# ethernet_hdmi.net
KiCad netlist of a schematic drawn in Altium Designer
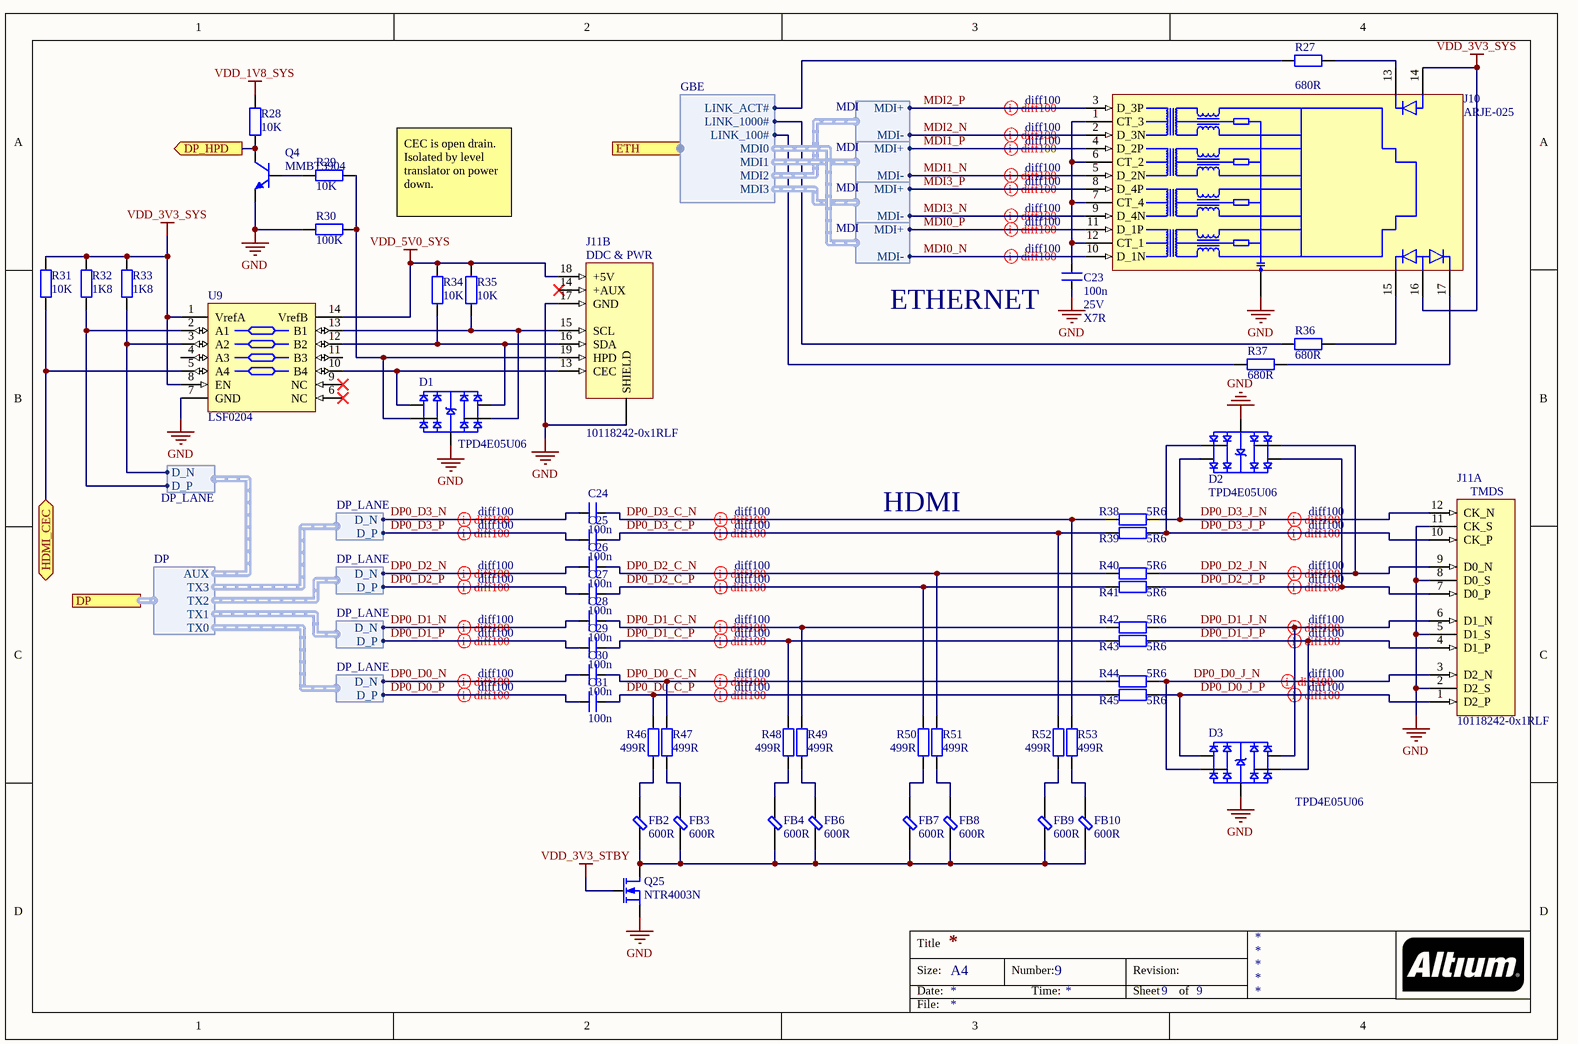
[diagram p0: ethernet_hdmi.SchDoc]

(export (version "E")
  (design (tool "Eeschema 10.0.6"))
  (components
    (comp (ref "C23")
      (value "100n")
      (footprint "C1005[0402]")
      (description "Capacitor")
      (fields (field (name "VOLTAGE") "25V") (field (name "TYPE") "X7R") (field (name "Comment") "cap"))
      (libsource (lib "gpa_passives") (part "cap"))
    )
    (comp (ref "C24")
      (value "100n")
      (footprint "C1005[0402]")
      (description "Capacitor")
      (fields (field (name "VOLTAGE") "25V") (field (name "Comment") "cap"))
      (libsource (lib "gpa_passives") (part "cap"))
    )
    (comp (ref "C25")
      (value "100n")
      (footprint "C1005[0402]")
      (description "Capacitor")
      (fields (field (name "VOLTAGE") "25V") (field (name "Comment") "cap"))
      (libsource (lib "gpa_passives") (part "cap"))
    )
    (comp (ref "C26")
      (value "100n")
      (footprint "C1005[0402]")
      (description "Capacitor")
      (fields (field (name "VOLTAGE") "25V") (field (name "Comment") "cap"))
      (libsource (lib "gpa_passives") (part "cap"))
    )
    (comp (ref "C27")
      (value "100n")
      (footprint "C1005[0402]")
      (description "Capacitor")
      (fields (field (name "VOLTAGE") "25V") (field (name "Comment") "cap"))
      (libsource (lib "gpa_passives") (part "cap"))
    )
    (comp (ref "C28")
      (value "100n")
      (footprint "C1005[0402]")
      (description "Capacitor")
      (fields (field (name "VOLTAGE") "25V") (field (name "Comment") "cap"))
      (libsource (lib "gpa_passives") (part "cap"))
    )
    (comp (ref "C29")
      (value "100n")
      (footprint "C1005[0402]")
      (description "Capacitor")
      (fields (field (name "VOLTAGE") "25V") (field (name "Comment") "cap"))
      (libsource (lib "gpa_passives") (part "cap"))
    )
    (comp (ref "C30")
      (value "100n")
      (footprint "C1005[0402]")
      (description "Capacitor")
      (fields (field (name "VOLTAGE") "25V") (field (name "Comment") "cap"))
      (libsource (lib "gpa_passives") (part "cap"))
    )
    (comp (ref "C31")
      (value "100n")
      (footprint "C1005[0402]")
      (description "Capacitor")
      (fields (field (name "VOLTAGE") "25V") (field (name "Comment") "cap"))
      (libsource (lib "gpa_passives") (part "cap"))
    )
    (comp (ref "D1")
      (value "TPD4E05U06")
      (footprint "TI_PSON50P100X55-10N")
      (libsource (lib "gpa_ti") (part "tpd4e05u06"))
    )
    (comp (ref "D2")
      (value "TPD4E05U06")
      (footprint "TI_PSON50P100X55-10N")
      (libsource (lib "gpa_ti") (part "tpd4e05u06"))
    )
    (comp (ref "D3")
      (value "TPD4E05U06")
      (footprint "TI_PSON50P100X55-10N")
      (libsource (lib "gpa_ti") (part "tpd4e05u06"))
    )
    (comp (ref "FB2")
      (value "600R")
      (footprint "FBC1608X07N")
      (description "Ferrite bead")
      (libsource (lib "gpa_passives") (part "ferrite_bead"))
    )
    (comp (ref "FB3")
      (value "600R")
      (footprint "FBC1608X07N")
      (description "Ferrite bead")
      (libsource (lib "gpa_passives") (part "ferrite_bead"))
    )
    (comp (ref "FB4")
      (value "600R")
      (footprint "FBC1608X07N")
      (description "Ferrite bead")
      (libsource (lib "gpa_passives") (part "ferrite_bead"))
    )
    (comp (ref "FB6")
      (value "600R")
      (footprint "FBC1608X07N")
      (description "Ferrite bead")
      (libsource (lib "gpa_passives") (part "ferrite_bead"))
    )
    (comp (ref "FB7")
      (value "600R")
      (footprint "FBC1608X07N")
      (description "Ferrite bead")
      (libsource (lib "gpa_passives") (part "ferrite_bead"))
    )
    (comp (ref "FB8")
      (value "600R")
      (footprint "FBC1608X07N")
      (description "Ferrite bead")
      (libsource (lib "gpa_passives") (part "ferrite_bead"))
    )
    (comp (ref "FB9")
      (value "600R")
      (footprint "FBC1608X07N")
      (description "Ferrite bead")
      (libsource (lib "gpa_passives") (part "ferrite_bead"))
    )
    (comp (ref "FB10")
      (value "600R")
      (footprint "FBC1608X07N")
      (description "Ferrite bead")
      (libsource (lib "gpa_passives") (part "ferrite_bead"))
    )
    (comp (ref "J10")
      (value "ARJE-025")
      (footprint "abraconn_rj45_arje0025")
      (description "RJ45 with integrated magnetics")
      (libsource (lib "gpa_connectors") (part "geth_wmagnetics"))
    )
    (comp (ref "J11")
      (value "10118242-0x1RLF")
      (footprint "molex_hdmi")
      (libsource (lib "gpa_connectors") (part "hdmi"))
    )
    (comp (ref "Q4")
      (value "MMBT3904")
      (footprint "NPN_SOT95P230X110-3N")
      (description "NPN Bipolar Transistor")
      (fields (field (name "PUBLISHER") "Altium Limited"))
      (libsource (lib "gpa_actives") (part "npn_bipolar"))
    )
    (comp (ref "Q25")
      (value "NTR4003N")
      (footprint "NCH_SOT95P237X110-3N")
      (libsource (lib "gpa_actives") (part "nch_mosfet"))
    )
    (comp (ref "R27")
      (value "680R")
      (footprint "R1005[0402]")
      (description "Resistor")
      (fields (field (name "Comment") "res"))
      (libsource (lib "") (part "res_1"))
    )
    (comp (ref "R28")
      (value "10K")
      (footprint "R1005[0402]")
      (description "Resistor")
      (fields (field (name "Comment") "res"))
      (libsource (lib "gpa_passives") (part "res"))
    )
    (comp (ref "R29")
      (value "10K")
      (footprint "R1005[0402]")
      (description "Resistor")
      (fields (field (name "Comment") "res"))
      (libsource (lib "") (part "res_1"))
    )
    (comp (ref "R30")
      (value "100K")
      (footprint "R1005[0402]")
      (description "Resistor")
      (fields (field (name "Comment") "res"))
      (libsource (lib "") (part "res_1"))
    )
    (comp (ref "R31")
      (value "10K")
      (footprint "R1005[0402]")
      (description "Resistor")
      (fields (field (name "Comment") "res"))
      (libsource (lib "gpa_passives") (part "res"))
    )
    (comp (ref "R32")
      (value "1K8")
      (footprint "R1005[0402]")
      (description "Resistor")
      (fields (field (name "Comment") "res"))
      (libsource (lib "gpa_passives") (part "res"))
    )
    (comp (ref "R33")
      (value "1K8")
      (footprint "R1005[0402]")
      (description "Resistor")
      (fields (field (name "Comment") "res"))
      (libsource (lib "gpa_passives") (part "res"))
    )
    (comp (ref "R34")
      (value "10K")
      (footprint "R1005[0402]")
      (description "Resistor")
      (fields (field (name "Comment") "res"))
      (libsource (lib "gpa_passives") (part "res"))
    )
    (comp (ref "R35")
      (value "10K")
      (footprint "R1005[0402]")
      (description "Resistor")
      (fields (field (name "Comment") "res"))
      (libsource (lib "gpa_passives") (part "res"))
    )
    (comp (ref "R36")
      (value "680R")
      (footprint "R1005[0402]")
      (description "Resistor")
      (fields (field (name "Comment") "res"))
      (libsource (lib "") (part "res_2"))
    )
    (comp (ref "R37")
      (value "680R")
      (footprint "R1005[0402]")
      (description "Resistor")
      (fields (field (name "Comment") "res"))
      (libsource (lib "") (part "res_1"))
    )
    (comp (ref "R38")
      (value "5R6")
      (footprint "R1005[0402]")
      (description "Resistor")
      (fields (field (name "Comment") "res"))
      (libsource (lib "") (part "res_2"))
    )
    (comp (ref "R39")
      (value "5R6")
      (footprint "R1005[0402]")
      (description "Resistor")
      (fields (field (name "Comment") "res"))
      (libsource (lib "") (part "res_2"))
    )
    (comp (ref "R40")
      (value "5R6")
      (footprint "R1005[0402]")
      (description "Resistor")
      (fields (field (name "Comment") "res"))
      (libsource (lib "") (part "res_2"))
    )
    (comp (ref "R41")
      (value "5R6")
      (footprint "R1005[0402]")
      (description "Resistor")
      (fields (field (name "Comment") "res"))
      (libsource (lib "") (part "res_2"))
    )
    (comp (ref "R42")
      (value "5R6")
      (footprint "R1005[0402]")
      (description "Resistor")
      (fields (field (name "Comment") "res"))
      (libsource (lib "") (part "res_2"))
    )
    (comp (ref "R43")
      (value "5R6")
      (footprint "R1005[0402]")
      (description "Resistor")
      (fields (field (name "Comment") "res"))
      (libsource (lib "") (part "res_2"))
    )
    (comp (ref "R44")
      (value "5R6")
      (footprint "R1005[0402]")
      (description "Resistor")
      (fields (field (name "Comment") "res"))
      (libsource (lib "") (part "res_2"))
    )
    (comp (ref "R45")
      (value "5R6")
      (footprint "R1005[0402]")
      (description "Resistor")
      (fields (field (name "Comment") "res"))
      (libsource (lib "") (part "res_2"))
    )
    (comp (ref "R46")
      (value "499R")
      (footprint "R1005[0402]")
      (description "Resistor")
      (fields (field (name "Comment") "res"))
      (libsource (lib "gpa_passives") (part "res"))
    )
    (comp (ref "R47")
      (value "499R")
      (footprint "R1005[0402]")
      (description "Resistor")
      (fields (field (name "Comment") "res"))
      (libsource (lib "gpa_passives") (part "res"))
    )
    (comp (ref "R48")
      (value "499R")
      (footprint "R1005[0402]")
      (description "Resistor")
      (fields (field (name "Comment") "res"))
      (libsource (lib "gpa_passives") (part "res"))
    )
    (comp (ref "R49")
      (value "499R")
      (footprint "R1005[0402]")
      (description "Resistor")
      (fields (field (name "Comment") "res"))
      (libsource (lib "gpa_passives") (part "res"))
    )
    (comp (ref "R50")
      (value "499R")
      (footprint "R1005[0402]")
      (description "Resistor")
      (fields (field (name "Comment") "res"))
      (libsource (lib "gpa_passives") (part "res"))
    )
    (comp (ref "R51")
      (value "499R")
      (footprint "R1005[0402]")
      (description "Resistor")
      (fields (field (name "Comment") "res"))
      (libsource (lib "gpa_passives") (part "res"))
    )
    (comp (ref "R52")
      (value "499R")
      (footprint "R1005[0402]")
      (description "Resistor")
      (fields (field (name "Comment") "res"))
      (libsource (lib "gpa_passives") (part "res"))
    )
    (comp (ref "R53")
      (value "499R")
      (footprint "R1005[0402]")
      (description "Resistor")
      (fields (field (name "Comment") "res"))
      (libsource (lib "gpa_passives") (part "res"))
    )
    (comp (ref "U9")
      (value "LSF0204")
      (footprint "TI_TSOP65P640X120-14N")
      (libsource (lib "gpa_ti") (part "lsf0204"))
    )
  )
  (nets
    (net (code "6") (name "/DP0_D0_C_N") (class "Default")
      (node (ref "C30") (pin "1") (pinfunction "1_1") (pintype "passive"))
      (node (ref "R44") (pin "1") (pinfunction "1_1") (pintype "passive"))
      (node (ref "R47") (pin "2") (pinfunction "2_2") (pintype "passive"))
    )
    (net (code "7") (name "/DP0_D0_C_P") (class "Default")
      (node (ref "C31") (pin "1") (pinfunction "1_1") (pintype "passive"))
      (node (ref "R45") (pin "1") (pinfunction "1_1") (pintype "passive"))
      (node (ref "R46") (pin "2") (pinfunction "2_2") (pintype "passive"))
    )
    (net (code "8") (name "/DP0_D0_J_N") (class "Default")
      (node (ref "D3") (pin "4") (pinfunction "D2-_4") (pintype "passive"))
      (node (ref "J11") (pin "3") (pinfunction "D2_N_3") (pintype "input"))
      (node (ref "R44") (pin "2") (pinfunction "2_2") (pintype "passive"))
    )
    (net (code "9") (name "/DP0_D0_J_P") (class "Default")
      (node (ref "D3") (pin "5") (pinfunction "D2+_5") (pintype "passive"))
      (node (ref "J11") (pin "1") (pinfunction "D2_P_1") (pintype "input"))
      (node (ref "R45") (pin "2") (pinfunction "2_2") (pintype "passive"))
    )
    (net (code "10") (name "/DP0_D0_N") (class "Default")
      (node (ref "C30") (pin "2") (pinfunction "2_2") (pintype "passive"))
    )
    (net (code "11") (name "/DP0_D0_P") (class "Default")
      (node (ref "C31") (pin "2") (pinfunction "2_2") (pintype "passive"))
    )
    (net (code "12") (name "/DP0_D1_C_N") (class "Default")
      (node (ref "C28") (pin "1") (pinfunction "1_1") (pintype "passive"))
      (node (ref "R42") (pin "1") (pinfunction "1_1") (pintype "passive"))
      (node (ref "R49") (pin "2") (pinfunction "2_2") (pintype "passive"))
    )
    (net (code "13") (name "/DP0_D1_C_P") (class "Default")
      (node (ref "C29") (pin "1") (pinfunction "1_1") (pintype "passive"))
      (node (ref "R43") (pin "1") (pinfunction "1_1") (pintype "passive"))
      (node (ref "R48") (pin "2") (pinfunction "2_2") (pintype "passive"))
    )
    (net (code "14") (name "/DP0_D1_J_N") (class "Default")
      (node (ref "D3") (pin "1") (pinfunction "D1+_1") (pintype "passive"))
      (node (ref "J11") (pin "6") (pinfunction "D1_N_6") (pintype "input"))
      (node (ref "R42") (pin "2") (pinfunction "2_2") (pintype "passive"))
    )
    (net (code "15") (name "/DP0_D1_J_P") (class "Default")
      (node (ref "D3") (pin "2") (pinfunction "D1-_2") (pintype "passive"))
      (node (ref "J11") (pin "4") (pinfunction "D1_P_4") (pintype "input"))
      (node (ref "R43") (pin "2") (pinfunction "2_2") (pintype "passive"))
    )
    (net (code "16") (name "/DP0_D1_N") (class "Default")
      (node (ref "C28") (pin "2") (pinfunction "2_2") (pintype "passive"))
    )
    (net (code "17") (name "/DP0_D1_P") (class "Default")
      (node (ref "C29") (pin "2") (pinfunction "2_2") (pintype "passive"))
    )
    (net (code "18") (name "/DP0_D2_C_N") (class "Default")
      (node (ref "C26") (pin "1") (pinfunction "1_1") (pintype "passive"))
      (node (ref "R40") (pin "1") (pinfunction "1_1") (pintype "passive"))
      (node (ref "R51") (pin "2") (pinfunction "2_2") (pintype "passive"))
    )
    (net (code "19") (name "/DP0_D2_C_P") (class "Default")
      (node (ref "C27") (pin "1") (pinfunction "1_1") (pintype "passive"))
      (node (ref "R41") (pin "1") (pinfunction "1_1") (pintype "passive"))
      (node (ref "R50") (pin "2") (pinfunction "2_2") (pintype "passive"))
    )
    (net (code "20") (name "/DP0_D2_J_N") (class "Default")
      (node (ref "D2") (pin "2") (pinfunction "D1-_2") (pintype "passive"))
      (node (ref "J11") (pin "9") (pinfunction "D0_N_9") (pintype "input"))
      (node (ref "R40") (pin "2") (pinfunction "2_2") (pintype "passive"))
    )
    (net (code "21") (name "/DP0_D2_J_P") (class "Default")
      (node (ref "D2") (pin "1") (pinfunction "D1+_1") (pintype "passive"))
      (node (ref "J11") (pin "7") (pinfunction "D0_P_7") (pintype "input"))
      (node (ref "R41") (pin "2") (pinfunction "2_2") (pintype "passive"))
    )
    (net (code "22") (name "/DP0_D2_N") (class "Default")
      (node (ref "C26") (pin "2") (pinfunction "2_2") (pintype "passive"))
    )
    (net (code "23") (name "/DP0_D2_P") (class "Default")
      (node (ref "C27") (pin "2") (pinfunction "2_2") (pintype "passive"))
    )
    (net (code "24") (name "/DP0_D3_C_N") (class "Default")
      (node (ref "C24") (pin "1") (pinfunction "1_1") (pintype "passive"))
      (node (ref "R38") (pin "1") (pinfunction "1_1") (pintype "passive"))
      (node (ref "R53") (pin "2") (pinfunction "2_2") (pintype "passive"))
    )
    (net (code "25") (name "/DP0_D3_C_P") (class "Default")
      (node (ref "C25") (pin "1") (pinfunction "1_1") (pintype "passive"))
      (node (ref "R39") (pin "1") (pinfunction "1_1") (pintype "passive"))
      (node (ref "R52") (pin "2") (pinfunction "2_2") (pintype "passive"))
    )
    (net (code "26") (name "/DP0_D3_J_N") (class "Default")
      (node (ref "D2") (pin "5") (pinfunction "D2+_5") (pintype "passive"))
      (node (ref "J11") (pin "12") (pinfunction "CK_N_12") (pintype "input"))
      (node (ref "R38") (pin "2") (pinfunction "2_2") (pintype "passive"))
    )
    (net (code "27") (name "/DP0_D3_J_P") (class "Default")
      (node (ref "D2") (pin "4") (pinfunction "D2-_4") (pintype "passive"))
      (node (ref "J11") (pin "10") (pinfunction "CK_P_10") (pintype "input"))
      (node (ref "R39") (pin "2") (pinfunction "2_2") (pintype "passive"))
    )
    (net (code "28") (name "/DP0_D3_N") (class "Default")
      (node (ref "C24") (pin "2") (pinfunction "2_2") (pintype "passive"))
    )
    (net (code "29") (name "/DP0_D3_P") (class "Default")
      (node (ref "C25") (pin "2") (pinfunction "2_2") (pintype "passive"))
    )
    (net (code "30") (name "/DP_HPD") (class "Default")
      (node (ref "Q4") (pin "C") (pinfunction "C_C") (pintype "passive"))
      (node (ref "R28") (pin "1") (pinfunction "1_1") (pintype "passive"))
    )
    (net (code "33") (name "/HDMI_CEC") (class "Default")
      (node (ref "R31") (pin "1") (pinfunction "1_1") (pintype "passive"))
      (node (ref "U9") (pin "5") (pinfunction "A4_5") (pintype "bidirectional"))
    )
    (net (code "34") (name "/LINK_100#") (class "Default")
      (node (ref "R37") (pin "2") (pinfunction "2_2") (pintype "passive"))
    )
    (net (code "35") (name "/LINK_1000#") (class "Default")
      (node (ref "R36") (pin "1") (pinfunction "1_1") (pintype "passive"))
    )
    (net (code "36") (name "/LINK_ACT#") (class "Default")
      (node (ref "R27") (pin "2") (pinfunction "2_2") (pintype "passive"))
    )
    (net (code "37") (name "/MDI0_N") (class "Default")
      (node (ref "J10") (pin "10") (pinfunction "D_1N_10") (pintype "input"))
    )
    (net (code "38") (name "/MDI0_P") (class "Default")
      (node (ref "J10") (pin "11") (pinfunction "D_1P_11") (pintype "input"))
    )
    (net (code "39") (name "/MDI1_N") (class "Default")
      (node (ref "J10") (pin "5") (pinfunction "D_2N_5") (pintype "input"))
    )
    (net (code "40") (name "/MDI1_P") (class "Default")
      (node (ref "J10") (pin "4") (pinfunction "D_2P_4") (pintype "input"))
    )
    (net (code "41") (name "/MDI2_N") (class "Default")
      (node (ref "J10") (pin "2") (pinfunction "D_3N_2") (pintype "input"))
    )
    (net (code "42") (name "/MDI2_P") (class "Default")
      (node (ref "J10") (pin "3") (pinfunction "D_3P_3") (pintype "input"))
    )
    (net (code "43") (name "/MDI3_N") (class "Default")
      (node (ref "J10") (pin "9") (pinfunction "D_4N_9") (pintype "input"))
    )
    (net (code "44") (name "/MDI3_P") (class "Default")
      (node (ref "J10") (pin "8") (pinfunction "D_4P_8") (pintype "input"))
    )
    (net (code "48") (name "GND") (class "Default")
      (node (ref "C23") (pin "1") (pinfunction "1_1") (pintype "passive"))
      (node (ref "D1") (pin "3") (pinfunction "GND_3") (pintype "passive"))
      (node (ref "D2") (pin "3") (pinfunction "GND_3") (pintype "passive"))
      (node (ref "D3") (pin "3") (pinfunction "GND_3") (pintype "passive"))
      (node (ref "J10") (pin "SHIELD") (pinfunction "SHIELD_SHIELD") (pintype "power_in"))
      (node (ref "J11") (pin "11") (pinfunction "CK_S_11") (pintype "power_in"))
      (node (ref "J11") (pin "17") (pinfunction "GND_17") (pintype "input"))
      (node (ref "J11") (pin "2") (pinfunction "D2_S_2") (pintype "power_in"))
      (node (ref "J11") (pin "5") (pinfunction "D1_S_5") (pintype "power_in"))
      (node (ref "J11") (pin "8") (pinfunction "D0_S_8") (pintype "power_in"))
      (node (ref "J11") (pin "SHIELD") (pinfunction "SHIELD_SHIELD") (pintype "passive"))
      (node (ref "Q25") (pin "S") (pinfunction "S_S") (pintype "passive"))
      (node (ref "Q4") (pin "E") (pinfunction "E_E") (pintype "passive"))
      (node (ref "R30") (pin "2") (pinfunction "2_2") (pintype "passive"))
      (node (ref "U9") (pin "7") (pinfunction "GND_7") (pintype "power_in"))
    )
    (net (code "49") (name "Net-(D1-D1+)") (class "Default")
      (node (ref "D1") (pin "1") (pinfunction "D1+_1") (pintype "passive"))
      (node (ref "J11") (pin "13") (pinfunction "CEC_13") (pintype "input"))
      (node (ref "U9") (pin "10") (pinfunction "B4_10") (pintype "bidirectional"))
    )
    (net (code "50") (name "Net-(D1-D1-)") (class "Default")
      (node (ref "D1") (pin "2") (pinfunction "D1-_2") (pintype "passive"))
      (node (ref "J11") (pin "19") (pinfunction "HPD_19") (pintype "input"))
      (node (ref "R29") (pin "1") (pinfunction "1_1") (pintype "passive"))
      (node (ref "R30") (pin "1") (pinfunction "1_1") (pintype "passive"))
    )
    (net (code "51") (name "Net-(D1-D2+)") (class "Default")
      (node (ref "D1") (pin "5") (pinfunction "D2+_5") (pintype "passive"))
      (node (ref "J11") (pin "16") (pinfunction "SDA_16") (pintype "input"))
      (node (ref "R34") (pin "1") (pinfunction "1_1") (pintype "passive"))
      (node (ref "U9") (pin "12") (pinfunction "B2_12") (pintype "bidirectional"))
    )
    (net (code "52") (name "Net-(D1-D2-)") (class "Default")
      (node (ref "D1") (pin "4") (pinfunction "D2-_4") (pintype "passive"))
      (node (ref "J11") (pin "15") (pinfunction "SCL_15") (pintype "input"))
      (node (ref "R35") (pin "1") (pinfunction "1_1") (pintype "passive"))
      (node (ref "U9") (pin "13") (pinfunction "B1_13") (pintype "bidirectional"))
    )
    (net (code "53") (name "Net-(FB2-Pad2)") (class "Default")
      (node (ref "FB2") (pin "2") (pinfunction "2_2") (pintype "passive"))
      (node (ref "R46") (pin "1") (pinfunction "1_1") (pintype "passive"))
    )
    (net (code "54") (name "Net-(FB3-Pad2)") (class "Default")
      (node (ref "FB3") (pin "2") (pinfunction "2_2") (pintype "passive"))
      (node (ref "R47") (pin "1") (pinfunction "1_1") (pintype "passive"))
    )
    (net (code "55") (name "Net-(FB4-Pad2)") (class "Default")
      (node (ref "FB4") (pin "2") (pinfunction "2_2") (pintype "passive"))
      (node (ref "R48") (pin "1") (pinfunction "1_1") (pintype "passive"))
    )
    (net (code "56") (name "Net-(FB6-Pad2)") (class "Default")
      (node (ref "FB6") (pin "2") (pinfunction "2_2") (pintype "passive"))
      (node (ref "R49") (pin "1") (pinfunction "1_1") (pintype "passive"))
    )
    (net (code "57") (name "Net-(FB7-Pad2)") (class "Default")
      (node (ref "FB7") (pin "2") (pinfunction "2_2") (pintype "passive"))
      (node (ref "R50") (pin "1") (pinfunction "1_1") (pintype "passive"))
    )
    (net (code "58") (name "Net-(FB8-Pad2)") (class "Default")
      (node (ref "FB8") (pin "2") (pinfunction "2_2") (pintype "passive"))
      (node (ref "R51") (pin "1") (pinfunction "1_1") (pintype "passive"))
    )
    (net (code "59") (name "Net-(FB9-Pad2)") (class "Default")
      (node (ref "FB9") (pin "2") (pinfunction "2_2") (pintype "passive"))
      (node (ref "R52") (pin "1") (pinfunction "1_1") (pintype "passive"))
    )
    (net (code "60") (name "Net-(FB10-Pad1)") (class "Default")
      (node (ref "FB10") (pin "1") (pinfunction "1_1") (pintype "passive"))
      (node (ref "FB2") (pin "1") (pinfunction "1_1") (pintype "passive"))
      (node (ref "FB3") (pin "1") (pinfunction "1_1") (pintype "passive"))
      (node (ref "FB4") (pin "1") (pinfunction "1_1") (pintype "passive"))
      (node (ref "FB6") (pin "1") (pinfunction "1_1") (pintype "passive"))
      (node (ref "FB7") (pin "1") (pinfunction "1_1") (pintype "passive"))
      (node (ref "FB8") (pin "1") (pinfunction "1_1") (pintype "passive"))
      (node (ref "FB9") (pin "1") (pinfunction "1_1") (pintype "passive"))
      (node (ref "Q25") (pin "D") (pinfunction "D_D") (pintype "passive"))
    )
    (net (code "61") (name "Net-(FB10-Pad2)") (class "Default")
      (node (ref "FB10") (pin "2") (pinfunction "2_2") (pintype "passive"))
      (node (ref "R53") (pin "1") (pinfunction "1_1") (pintype "passive"))
    )
    (net (code "62") (name "Net-(J10-CT_1)") (class "Default")
      (node (ref "C23") (pin "2") (pinfunction "2_2") (pintype "passive"))
      (node (ref "J10") (pin "1") (pinfunction "CT_3_1") (pintype "passive"))
      (node (ref "J10") (pin "12") (pinfunction "CT_1_12") (pintype "passive"))
      (node (ref "J10") (pin "6") (pinfunction "CT_2_6") (pintype "passive"))
      (node (ref "J10") (pin "7") (pinfunction "CT_4_7") (pintype "passive"))
    )
    (net (code "63") (name "Net-(J10-Pad13)") (class "Default")
      (node (ref "J10") (pin "13") (pinfunction "13_13") (pintype "passive"))
      (node (ref "R27") (pin "1") (pinfunction "1_1") (pintype "passive"))
    )
    (net (code "64") (name "Net-(J10-Pad15)") (class "Default")
      (node (ref "J10") (pin "15") (pinfunction "15_15") (pintype "passive"))
      (node (ref "R36") (pin "2") (pinfunction "2_2") (pintype "passive"))
    )
    (net (code "65") (name "Net-(J10-Pad17)") (class "Default")
      (node (ref "J10") (pin "17") (pinfunction "17_17") (pintype "passive"))
      (node (ref "R37") (pin "1") (pinfunction "1_1") (pintype "passive"))
    )
    (net (code "66") (name "Net-(Q4-PadB)") (class "Default")
      (node (ref "Q4") (pin "B") (pinfunction "B_B") (pintype "passive"))
      (node (ref "R29") (pin "2") (pinfunction "2_2") (pintype "passive"))
    )
    (net (code "67") (name "Net-(U9-A1)") (class "Default")
      (node (ref "R32") (pin "1") (pinfunction "1_1") (pintype "passive"))
      (node (ref "U9") (pin "2") (pinfunction "A1_2") (pintype "bidirectional"))
    )
    (net (code "68") (name "Net-(U9-A2)") (class "Default")
      (node (ref "R33") (pin "1") (pinfunction "1_1") (pintype "passive"))
      (node (ref "U9") (pin "3") (pinfunction "A2_3") (pintype "bidirectional"))
    )
    (net (code "69") (name "VDD_1V8_SYS") (class "Default")
      (node (ref "R28") (pin "2") (pinfunction "2_2") (pintype "passive"))
    )
    (net (code "70") (name "VDD_3V3_STBY") (class "Default")
      (node (ref "Q25") (pin "G") (pinfunction "G_G") (pintype "passive"))
    )
    (net (code "71") (name "VDD_3V3_SYS") (class "Default")
      (node (ref "J10") (pin "14") (pinfunction "14_14") (pintype "passive"))
      (node (ref "J10") (pin "16") (pinfunction "16_16") (pintype "passive"))
      (node (ref "R31") (pin "2") (pinfunction "2_2") (pintype "passive"))
      (node (ref "R32") (pin "2") (pinfunction "2_2") (pintype "passive"))
      (node (ref "R33") (pin "2") (pinfunction "2_2") (pintype "passive"))
      (node (ref "U9") (pin "1") (pinfunction "VrefA_1") (pintype "power_in"))
      (node (ref "U9") (pin "8") (pinfunction "EN_8") (pintype "input"))
    )
    (net (code "72") (name "VDD_5V0_SYS") (class "Default")
      (node (ref "J11") (pin "18") (pinfunction "+5V_18") (pintype "input"))
      (node (ref "R34") (pin "2") (pinfunction "2_2") (pintype "passive"))
      (node (ref "R35") (pin "2") (pinfunction "2_2") (pintype "passive"))
      (node (ref "U9") (pin "14") (pinfunction "VrefB_14") (pintype "power_in"))
    )
    (net (code "73") (name "unconnected-(J11B-+AUX-Pad14)") (class "Default")
      (node (ref "J11") (pin "14") (pinfunction "+AUX_14") (pintype "input+no_connect"))
    )
    (net (code "74") (name "unconnected-(U9-A3-Pad4)") (class "Default")
      (node (ref "U9") (pin "4") (pinfunction "A3_4") (pintype "bidirectional"))
    )
    (net (code "75") (name "unconnected-(U9-B3-Pad11)") (class "Default")
      (node (ref "U9") (pin "11") (pinfunction "B3_11") (pintype "bidirectional"))
    )
    (net (code "76") (name "unconnected-(U9-NC-Pad6)") (class "Default")
      (node (ref "U9") (pin "6") (pinfunction "NC_6") (pintype "input+no_connect"))
    )
    (net (code "77") (name "unconnected-(U9-NC-Pad9)") (class "Default")
      (node (ref "U9") (pin "9") (pinfunction "NC_9") (pintype "input+no_connect"))
    )
  )
)
